# Main_PCB.net
KiCad netlist of a schematic drawn in EAGLE
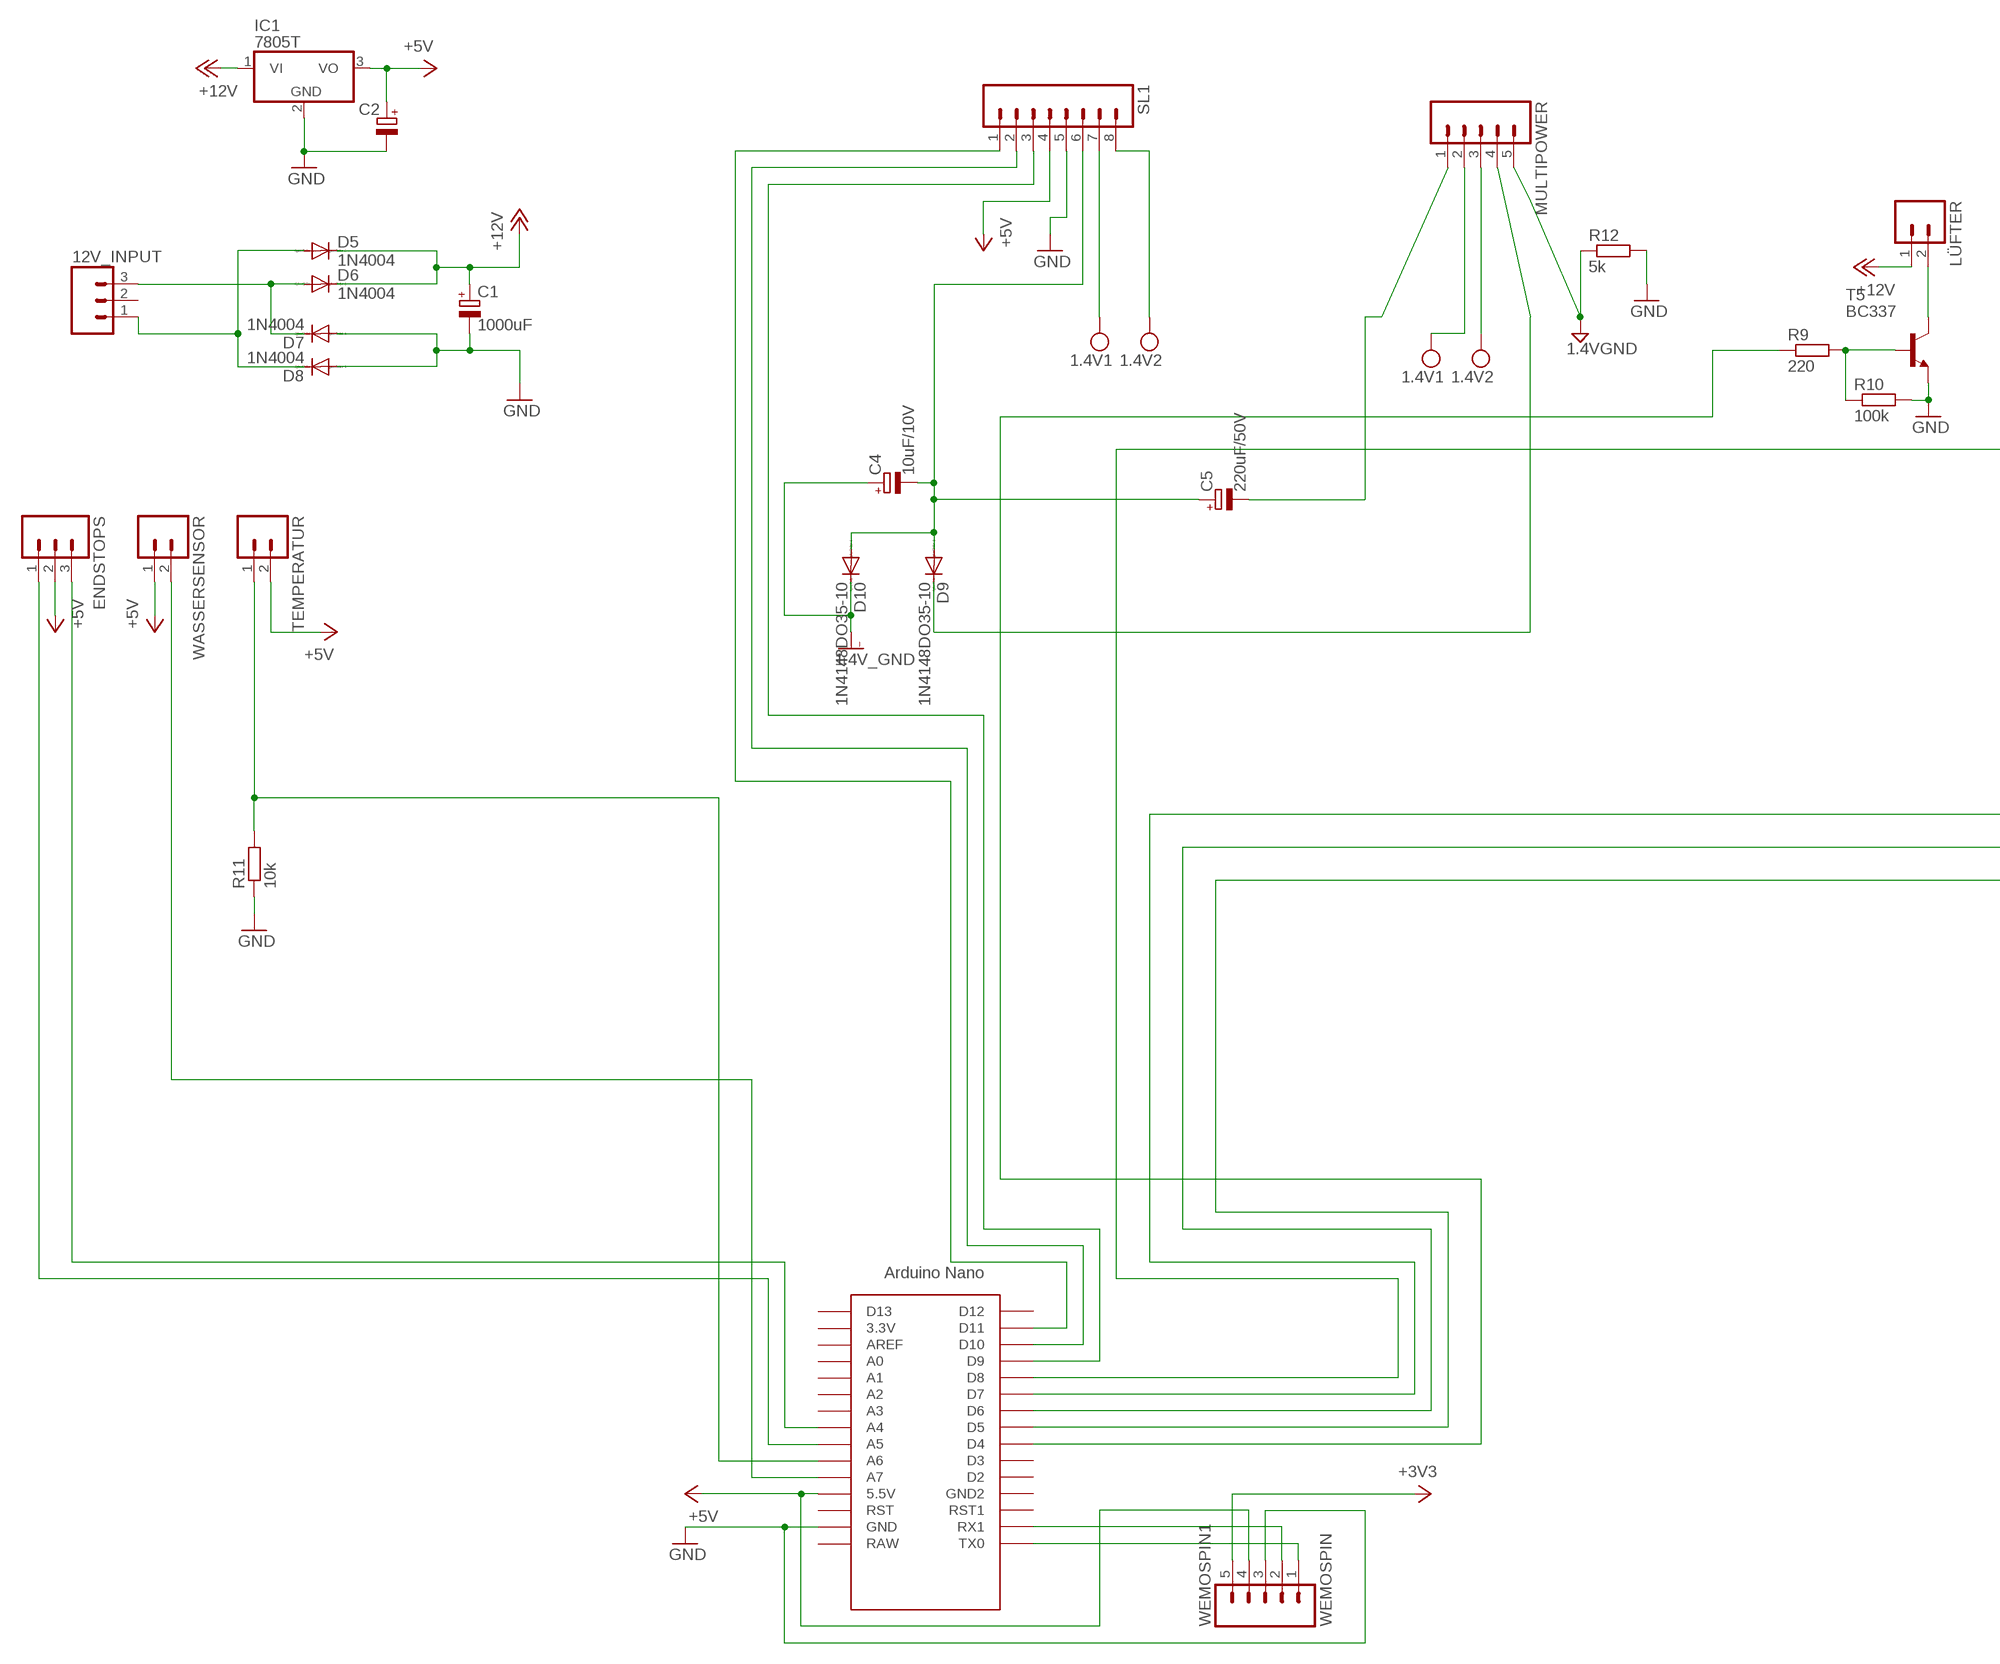
[diagram p0: schematic, sheet 1, part 1 of 2]
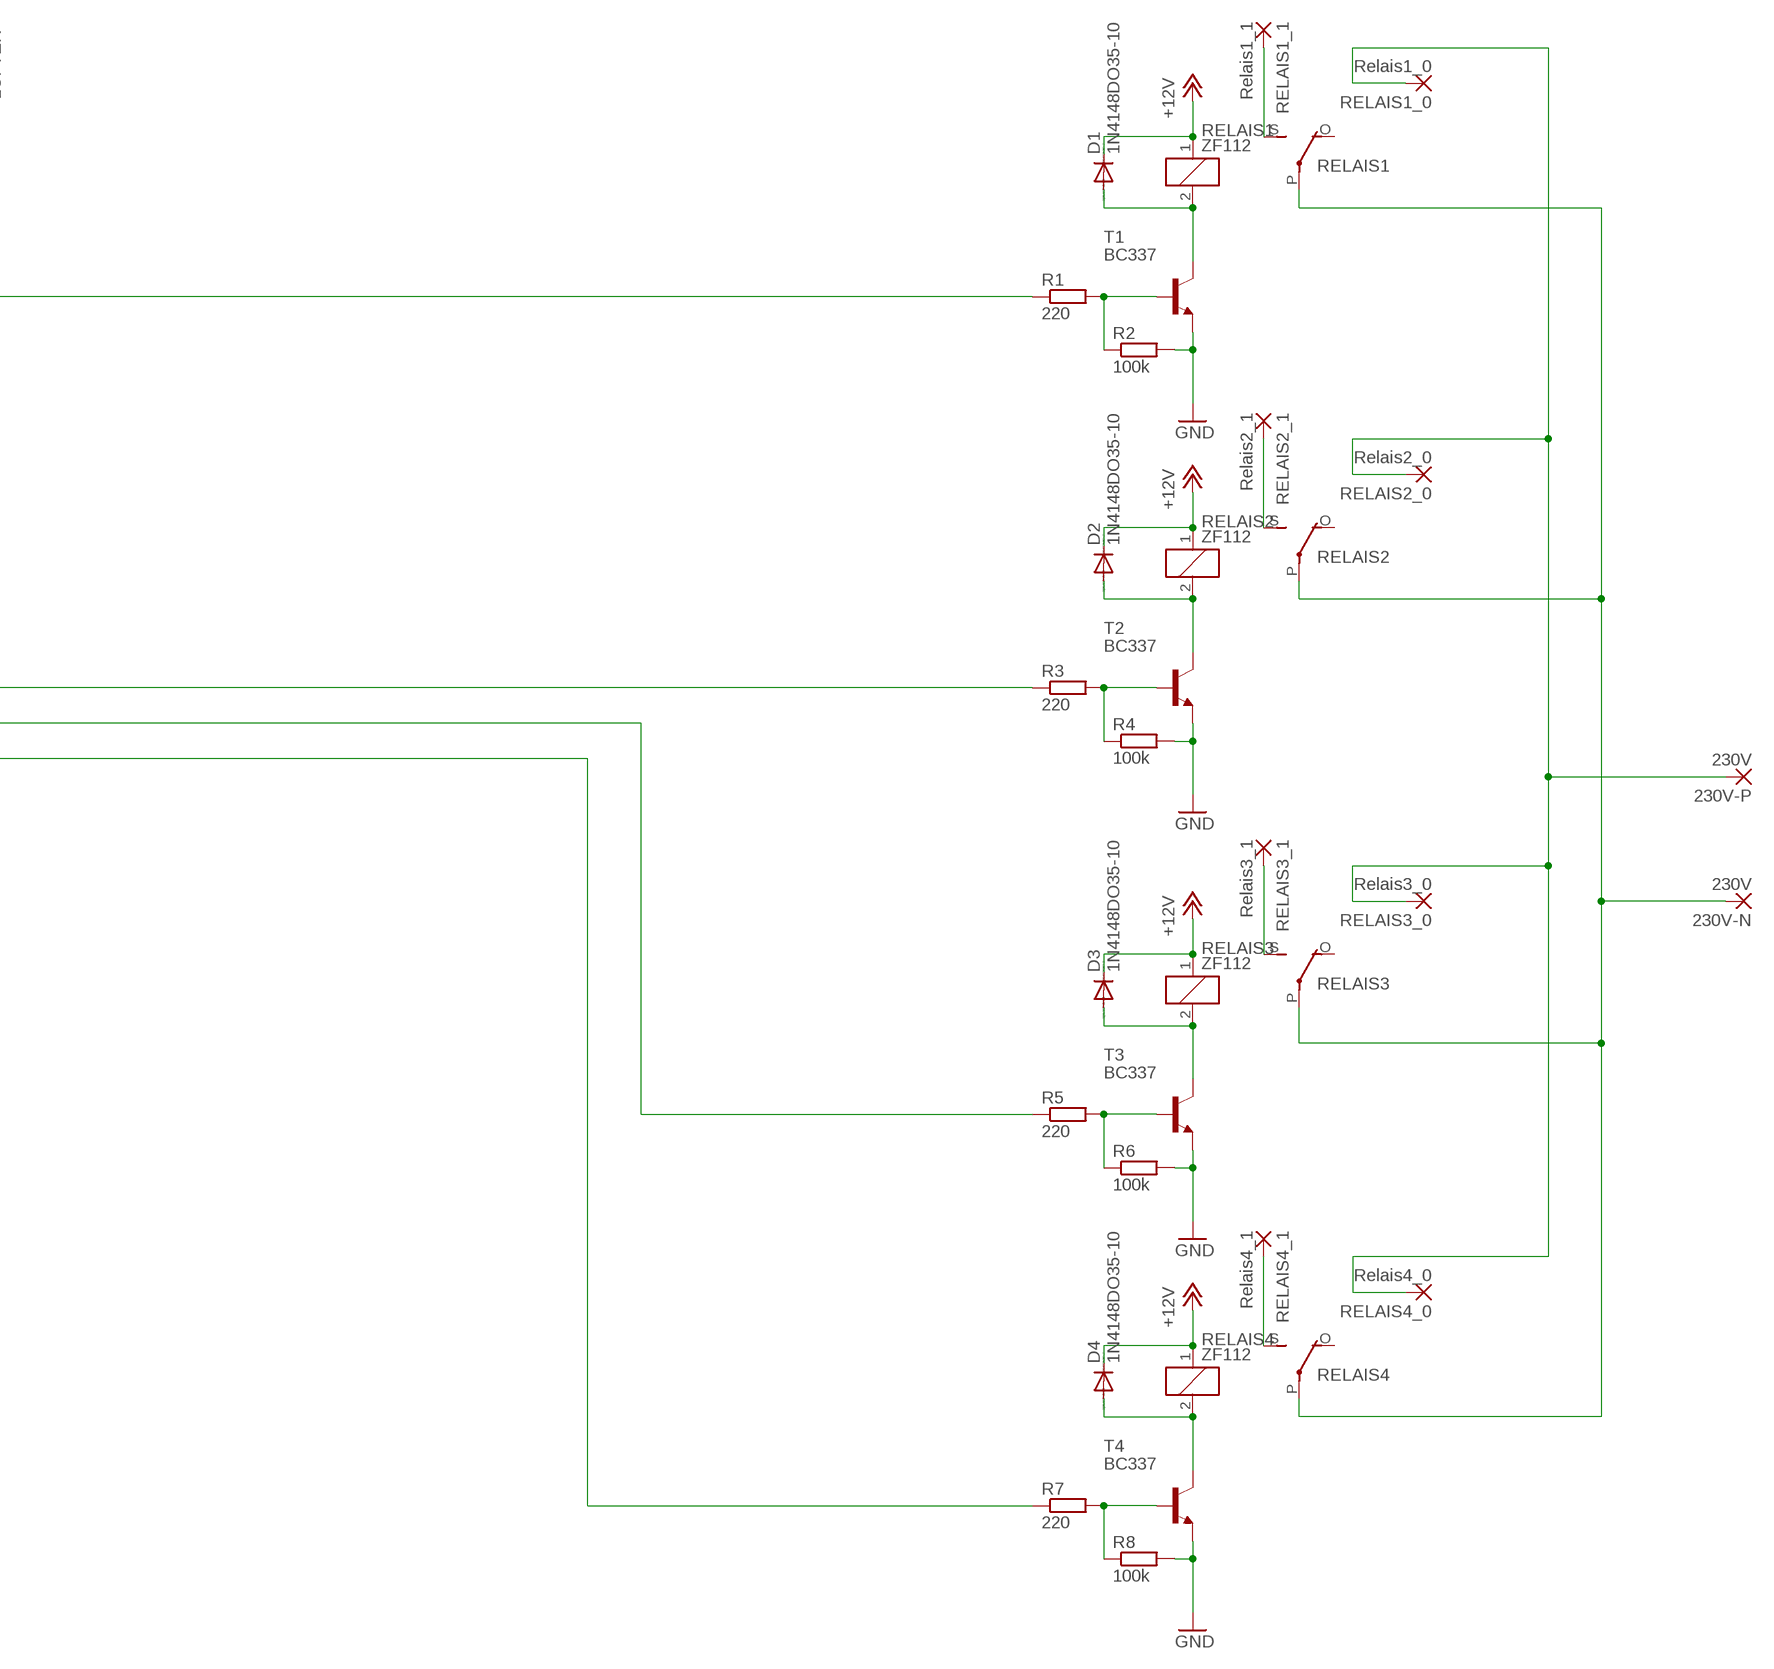
[diagram p1: schematic, sheet 1, part 2 of 2]

(export (version "E")
  (design (tool "Eeschema 10.0.6"))
  (components
    (comp (ref "12V_INPUT")
      (value "M03")
      (footprint "eagle-import:03P")
      (libsource (lib "eagle-import") (part "M03"))
    )
    (comp (ref "230V-N")
      (value "230V")
      (footprint "eagle-import:2,15_1,0")
      (libsource (lib "eagle-import") (part "2,15/1,0"))
    )
    (comp (ref "230V-P")
      (value "230V")
      (footprint "eagle-import:2,15_1,0")
      (libsource (lib "eagle-import") (part "2,15/1,0"))
    )
    (comp (ref "C1")
      (value "1000uF")
      (footprint "eagle-import:E2,5-5")
      (libsource (lib "eagle-import") (part "CPOL-EUE2.5-5"))
    )
    (comp (ref "C2")
      (value "CPOL-EUE2.5-4V")
      (footprint "eagle-import:E2,5RE")
      (libsource (lib "eagle-import") (part "resistor_348_CPOL-EUE2.5-4V"))
    )
    (comp (ref "C4")
      (value "10uF/10V")
      (footprint "eagle-import:E2,5RE")
      (libsource (lib "eagle-import") (part "CPOL-EUE2.5-4V"))
    )
    (comp (ref "C5")
      (value "220uF/50V")
      (footprint "eagle-import:E2,5RE")
      (libsource (lib "eagle-import") (part "CPOL-EUE2.5-4V"))
    )
    (comp (ref "D1")
      (value "1N4148DO35-10")
      (footprint "eagle-import:DO35-10")
      (libsource (lib "eagle-import") (part "1N4148DO35-10"))
    )
    (comp (ref "D2")
      (value "1N4148DO35-10")
      (footprint "eagle-import:DO35-10")
      (libsource (lib "eagle-import") (part "1N4148DO35-10"))
    )
    (comp (ref "D3")
      (value "1N4148DO35-10")
      (footprint "eagle-import:DO35-10")
      (libsource (lib "eagle-import") (part "1N4148DO35-10"))
    )
    (comp (ref "D4")
      (value "1N4148DO35-10")
      (footprint "eagle-import:DO35-10")
      (libsource (lib "eagle-import") (part "1N4148DO35-10"))
    )
    (comp (ref "D5")
      (value "1N4004")
      (footprint "eagle-import:DO41-10")
      (libsource (lib "eagle-import") (part "1N4004"))
    )
    (comp (ref "D6")
      (value "1N4004")
      (footprint "eagle-import:DO41-10")
      (libsource (lib "eagle-import") (part "1N4004"))
    )
    (comp (ref "D7")
      (value "1N4004")
      (footprint "eagle-import:DO41-10")
      (libsource (lib "eagle-import") (part "1N4004"))
    )
    (comp (ref "D8")
      (value "1N4004")
      (footprint "eagle-import:DO41-10")
      (libsource (lib "eagle-import") (part "1N4004"))
    )
    (comp (ref "D9")
      (value "1N4148DO35-10")
      (footprint "eagle-import:DO35-10")
      (libsource (lib "eagle-import") (part "1N4148DO35-10"))
    )
    (comp (ref "D10")
      (value "1N4148DO35-10")
      (footprint "eagle-import:DO35-10")
      (libsource (lib "eagle-import") (part "1N4148DO35-10"))
    )
    (comp (ref "ENDSTOPS")
      (value "M03")
      (footprint "eagle-import:03P")
      (libsource (lib "eagle-import") (part "M03"))
    )
    (comp (ref "IC1")
      (value "7805T")
      (footprint "eagle-import:TO220H")
      (libsource (lib "eagle-import") (part "78T05"))
    )
    (comp (ref "LÜFTER")
      (value "M02")
      (footprint "eagle-import:02P")
      (libsource (lib "eagle-import") (part "M02"))
    )
    (comp (ref "MULTIPOWER")
      (value "M05")
      (footprint "eagle-import:05P")
      (libsource (lib "eagle-import") (part "M05"))
    )
    (comp (ref "R1")
      (value "220")
      (footprint "eagle-import:0207_10")
      (libsource (lib "eagle-import") (part "R-EU_0207/10"))
    )
    (comp (ref "R2")
      (value "100k")
      (footprint "eagle-import:0207_10")
      (libsource (lib "eagle-import") (part "R-EU_0207/10"))
    )
    (comp (ref "R3")
      (value "220")
      (footprint "eagle-import:0207_10")
      (libsource (lib "eagle-import") (part "R-EU_0207/10"))
    )
    (comp (ref "R4")
      (value "100k")
      (footprint "eagle-import:0207_10")
      (libsource (lib "eagle-import") (part "R-EU_0207/10"))
    )
    (comp (ref "R5")
      (value "220")
      (footprint "eagle-import:0207_10")
      (libsource (lib "eagle-import") (part "R-EU_0207/10"))
    )
    (comp (ref "R6")
      (value "100k")
      (footprint "eagle-import:0207_10")
      (libsource (lib "eagle-import") (part "R-EU_0207/10"))
    )
    (comp (ref "R7")
      (value "220")
      (footprint "eagle-import:0207_10")
      (libsource (lib "eagle-import") (part "R-EU_0207/10"))
    )
    (comp (ref "R8")
      (value "100k")
      (footprint "eagle-import:0207_10")
      (libsource (lib "eagle-import") (part "R-EU_0207/10"))
    )
    (comp (ref "R9")
      (value "220")
      (footprint "eagle-import:0207_10")
      (libsource (lib "eagle-import") (part "R-EU_0207/10"))
    )
    (comp (ref "R10")
      (value "100k")
      (footprint "eagle-import:0207_10")
      (libsource (lib "eagle-import") (part "R-EU_0207/10"))
    )
    (comp (ref "R11")
      (value "10k")
      (footprint "eagle-import:0207_10")
      (libsource (lib "eagle-import") (part "R-EU_0207/10"))
    )
    (comp (ref "R12")
      (value "5k")
      (footprint "eagle-import:0207_10")
      (libsource (lib "eagle-import") (part "R-EU_0207/10"))
    )
    (comp (ref "RELAIS1")
      (value "ZF112")
      (footprint "eagle-import:ZF112")
      (libsource (lib "eagle-import") (part "ZF112"))
    )
    (comp (ref "RELAIS1_0")
      (value "Relais1_0")
      (footprint "eagle-import:2,15_1,0")
      (libsource (lib "eagle-import") (part "2,15/1,0"))
    )
    (comp (ref "RELAIS1_1")
      (value "Relais1_1")
      (footprint "eagle-import:2,15_1,0")
      (libsource (lib "eagle-import") (part "2,15/1,0"))
    )
    (comp (ref "RELAIS2")
      (value "ZF112")
      (footprint "eagle-import:ZF112")
      (libsource (lib "eagle-import") (part "ZF112"))
    )
    (comp (ref "RELAIS2_0")
      (value "Relais2_0")
      (footprint "eagle-import:2,15_1,0")
      (libsource (lib "eagle-import") (part "2,15/1,0"))
    )
    (comp (ref "RELAIS2_1")
      (value "Relais2_1")
      (footprint "eagle-import:2,15_1,0")
      (libsource (lib "eagle-import") (part "2,15/1,0"))
    )
    (comp (ref "RELAIS3")
      (value "ZF112")
      (footprint "eagle-import:ZF112")
      (libsource (lib "eagle-import") (part "ZF112"))
    )
    (comp (ref "RELAIS3_0")
      (value "Relais3_0")
      (footprint "eagle-import:2,15_1,0")
      (libsource (lib "eagle-import") (part "2,15/1,0"))
    )
    (comp (ref "RELAIS3_1")
      (value "Relais3_1")
      (footprint "eagle-import:2,15_1,0")
      (libsource (lib "eagle-import") (part "2,15/1,0"))
    )
    (comp (ref "RELAIS4")
      (value "ZF112")
      (footprint "eagle-import:ZF112")
      (libsource (lib "eagle-import") (part "ZF112"))
    )
    (comp (ref "RELAIS4_0")
      (value "Relais4_0")
      (footprint "eagle-import:2,15_1,0")
      (libsource (lib "eagle-import") (part "2,15/1,0"))
    )
    (comp (ref "RELAIS4_1")
      (value "Relais4_1")
      (footprint "eagle-import:2,15_1,0")
      (libsource (lib "eagle-import") (part "2,15/1,0"))
    )
    (comp (ref "SL1")
      (value "M08")
      (footprint "eagle-import:08P")
      (libsource (lib "eagle-import") (part "M08"))
    )
    (comp (ref "T1")
      (value "BC337")
      (footprint "eagle-import:TO92")
      (libsource (lib "eagle-import") (part "BC337"))
    )
    (comp (ref "T2")
      (value "BC337")
      (footprint "eagle-import:TO92")
      (libsource (lib "eagle-import") (part "BC337"))
    )
    (comp (ref "T3")
      (value "BC337")
      (footprint "eagle-import:TO92")
      (libsource (lib "eagle-import") (part "BC337"))
    )
    (comp (ref "T4")
      (value "BC337")
      (footprint "eagle-import:TO92")
      (libsource (lib "eagle-import") (part "BC337"))
    )
    (comp (ref "T5")
      (value "BC337")
      (footprint "eagle-import:TO92")
      (libsource (lib "eagle-import") (part "BC337"))
    )
    (comp (ref "TEMPERATUR")
      (value "M02")
      (footprint "eagle-import:02P")
      (libsource (lib "eagle-import") (part "M02"))
    )
    (comp (ref "U$1")
      (value "NANO")
      (footprint "eagle-import:NANO")
      (libsource (lib "eagle-import") (part "NANO"))
    )
    (comp (ref "WASSERSENSOR")
      (value "M02")
      (footprint "eagle-import:02P")
      (libsource (lib "eagle-import") (part "M02"))
    )
    (comp (ref "WEMOSPIN1")
      (value "WEMOSPIN")
      (footprint "eagle-import:05P")
      (libsource (lib "eagle-import") (part "M05"))
    )
  )
  (nets
    (net (code "1") (name "+3V3") (class "Default")
      (node (ref "WEMOSPIN1") (pin "5") (pinfunction "5_5") (pintype "passive"))
    )
    (net (code "2") (name "+5V") (class "Default")
      (node (ref "C2") (pin "+") (pinfunction "+_+") (pintype "passive"))
      (node (ref "ENDSTOPS") (pin "2") (pinfunction "2_2") (pintype "passive"))
      (node (ref "IC1") (pin "3") (pinfunction "VO_3") (pintype "passive"))
      (node (ref "SL1") (pin "4") (pinfunction "4_4") (pintype "passive"))
      (node (ref "TEMPERATUR") (pin "2") (pinfunction "2_2") (pintype "passive"))
      (node (ref "U$1") (pin "5V") (pinfunction "5.5V_5V") (pintype "bidirectional"))
      (node (ref "WASSERSENSOR") (pin "1") (pinfunction "1_1") (pintype "passive"))
      (node (ref "WEMOSPIN1") (pin "4") (pinfunction "4_4") (pintype "passive"))
    )
    (net (code "3") (name "+12V") (class "Default")
      (node (ref "C1") (pin "+") (pinfunction "+_+") (pintype "passive"))
      (node (ref "D1") (pin "C") (pinfunction "C_C") (pintype "passive"))
      (node (ref "D2") (pin "C") (pinfunction "C_C") (pintype "passive"))
      (node (ref "D3") (pin "C") (pinfunction "C_C") (pintype "passive"))
      (node (ref "D4") (pin "C") (pinfunction "C_C") (pintype "passive"))
      (node (ref "D5") (pin "C") (pinfunction "C_C") (pintype "passive"))
      (node (ref "D6") (pin "C") (pinfunction "C_C") (pintype "passive"))
      (node (ref "IC1") (pin "1") (pinfunction "VI_1") (pintype "input"))
      (node (ref "LÜFTER") (pin "1") (pinfunction "1_1") (pintype "passive"))
      (node (ref "RELAIS1") (pin "1") (pinfunction "1_1") (pintype "passive"))
      (node (ref "RELAIS2") (pin "1") (pinfunction "1_1") (pintype "passive"))
      (node (ref "RELAIS3") (pin "1") (pinfunction "1_1") (pintype "passive"))
      (node (ref "RELAIS4") (pin "1") (pinfunction "1_1") (pintype "passive"))
    )
    (net (code "4") (name "1.4V1") (class "Default")
      (node (ref "MULTIPOWER") (pin "2") (pinfunction "2_2") (pintype "passive"))
      (node (ref "SL1") (pin "7") (pinfunction "7_7") (pintype "passive"))
    )
    (net (code "5") (name "1.4V2") (class "Default")
      (node (ref "MULTIPOWER") (pin "3") (pinfunction "3_3") (pintype "passive"))
      (node (ref "SL1") (pin "8") (pinfunction "8_8") (pintype "passive"))
    )
    (net (code "6") (name "1.4VGND") (class "Default")
      (node (ref "MULTIPOWER") (pin "5") (pinfunction "5_5") (pintype "passive"))
      (node (ref "R12") (pin "1") (pinfunction "1_1") (pintype "passive"))
    )
    (net (code "7") (name "1.4V_GND") (class "Default")
      (node (ref "C4") (pin "+") (pinfunction "+_+") (pintype "passive"))
      (node (ref "D10") (pin "C") (pinfunction "C_C") (pintype "passive"))
    )
    (net (code "8") (name "GND") (class "Default")
      (node (ref "C1") (pin "-") (pinfunction "-_-") (pintype "passive"))
      (node (ref "C2") (pin "-") (pinfunction "-_-") (pintype "passive"))
      (node (ref "D7") (pin "A") (pinfunction "A_A") (pintype "passive"))
      (node (ref "D8") (pin "A") (pinfunction "A_A") (pintype "passive"))
      (node (ref "IC1") (pin "2") (pinfunction "GND_2") (pintype "passive"))
      (node (ref "R10") (pin "2") (pinfunction "2_2") (pintype "passive"))
      (node (ref "R11") (pin "1") (pinfunction "1_1") (pintype "passive"))
      (node (ref "R12") (pin "2") (pinfunction "2_2") (pintype "passive"))
      (node (ref "R2") (pin "2") (pinfunction "2_2") (pintype "passive"))
      (node (ref "R4") (pin "2") (pinfunction "2_2") (pintype "passive"))
      (node (ref "R6") (pin "2") (pinfunction "2_2") (pintype "passive"))
      (node (ref "R8") (pin "2") (pinfunction "2_2") (pintype "passive"))
      (node (ref "SL1") (pin "5") (pinfunction "5_5") (pintype "passive"))
      (node (ref "T1") (pin "1") (pinfunction "E_1") (pintype "passive"))
      (node (ref "T2") (pin "1") (pinfunction "E_1") (pintype "passive"))
      (node (ref "T3") (pin "1") (pinfunction "E_1") (pintype "passive"))
      (node (ref "T4") (pin "1") (pinfunction "E_1") (pintype "passive"))
      (node (ref "T5") (pin "1") (pinfunction "E_1") (pintype "passive"))
      (node (ref "U$1") (pin "GND") (pinfunction "GND_GND") (pintype "bidirectional"))
      (node (ref "WEMOSPIN1") (pin "3") (pinfunction "3_3") (pintype "passive"))
    )
    (net (code "9") (name "Net-(12V_INPUT-Pad1)") (class "Default")
      (node (ref "12V_INPUT") (pin "1") (pinfunction "1_1") (pintype "passive"))
      (node (ref "D5") (pin "A") (pinfunction "A_A") (pintype "passive"))
      (node (ref "D8") (pin "C") (pinfunction "C_C") (pintype "passive"))
    )
    (net (code "10") (name "Net-(12V_INPUT-Pad3)") (class "Default")
      (node (ref "12V_INPUT") (pin "3") (pinfunction "3_3") (pintype "passive"))
      (node (ref "D6") (pin "A") (pinfunction "A_A") (pintype "passive"))
      (node (ref "D7") (pin "C") (pinfunction "C_C") (pintype "passive"))
    )
    (net (code "11") (name "Net-(230V-N-P)") (class "Default")
      (node (ref "230V-N") (pin "1") (pinfunction "P_1") (pintype "passive"))
      (node (ref "RELAIS1") (pin "P") (pinfunction "P_P") (pintype "passive"))
      (node (ref "RELAIS2") (pin "P") (pinfunction "P_P") (pintype "passive"))
      (node (ref "RELAIS3") (pin "P") (pinfunction "P_P") (pintype "passive"))
      (node (ref "RELAIS4") (pin "P") (pinfunction "P_P") (pintype "passive"))
    )
    (net (code "12") (name "Net-(230V-P-P)") (class "Default")
      (node (ref "230V-P") (pin "1") (pinfunction "P_1") (pintype "passive"))
      (node (ref "RELAIS1_0") (pin "1") (pinfunction "P_1") (pintype "passive"))
      (node (ref "RELAIS2_0") (pin "1") (pinfunction "P_1") (pintype "passive"))
      (node (ref "RELAIS3_0") (pin "1") (pinfunction "P_1") (pintype "passive"))
      (node (ref "RELAIS4_0") (pin "1") (pinfunction "P_1") (pintype "passive"))
    )
    (net (code "13") (name "Net-(C4-Pad-)") (class "Default")
      (node (ref "C4") (pin "-") (pinfunction "-_-") (pintype "passive"))
      (node (ref "C5") (pin "+") (pinfunction "+_+") (pintype "passive"))
      (node (ref "D10") (pin "A") (pinfunction "A_A") (pintype "passive"))
      (node (ref "D9") (pin "A") (pinfunction "A_A") (pintype "passive"))
      (node (ref "SL1") (pin "6") (pinfunction "6_6") (pintype "passive"))
    )
    (net (code "14") (name "Net-(C5-Pad-)") (class "Default")
      (node (ref "C5") (pin "-") (pinfunction "-_-") (pintype "passive"))
      (node (ref "MULTIPOWER") (pin "1") (pinfunction "1_1") (pintype "passive"))
    )
    (net (code "15") (name "Net-(D9-PadC)") (class "Default")
      (node (ref "D9") (pin "C") (pinfunction "C_C") (pintype "passive"))
      (node (ref "MULTIPOWER") (pin "4") (pinfunction "4_4") (pintype "passive"))
    )
    (net (code "16") (name "Net-(ENDSTOPS-Pad1)") (class "Default")
      (node (ref "ENDSTOPS") (pin "1") (pinfunction "1_1") (pintype "passive"))
      (node (ref "U$1") (pin "A5") (pinfunction "A5_A5") (pintype "bidirectional"))
    )
    (net (code "17") (name "Net-(ENDSTOPS-Pad3)") (class "Default")
      (node (ref "ENDSTOPS") (pin "3") (pinfunction "3_3") (pintype "passive"))
      (node (ref "U$1") (pin "A4") (pinfunction "A4_A4") (pintype "bidirectional"))
    )
    (net (code "18") (name "Net-(R1-Pad1)") (class "Default")
      (node (ref "R1") (pin "1") (pinfunction "1_1") (pintype "passive"))
      (node (ref "U$1") (pin "D8") (pinfunction "D8_D8") (pintype "bidirectional"))
    )
    (net (code "19") (name "Net-(R3-Pad1)") (class "Default")
      (node (ref "R3") (pin "1") (pinfunction "1_1") (pintype "passive"))
      (node (ref "U$1") (pin "D7") (pinfunction "D7_D7") (pintype "bidirectional"))
    )
    (net (code "20") (name "Net-(R5-Pad1)") (class "Default")
      (node (ref "R5") (pin "1") (pinfunction "1_1") (pintype "passive"))
      (node (ref "U$1") (pin "D6") (pinfunction "D6_D6") (pintype "bidirectional"))
    )
    (net (code "21") (name "Net-(R7-Pad1)") (class "Default")
      (node (ref "R7") (pin "1") (pinfunction "1_1") (pintype "passive"))
      (node (ref "U$1") (pin "D5") (pinfunction "D5_D5") (pintype "bidirectional"))
    )
    (net (code "22") (name "Net-(R9-Pad1)") (class "Default")
      (node (ref "R9") (pin "1") (pinfunction "1_1") (pintype "passive"))
      (node (ref "U$1") (pin "D4") (pinfunction "D4_D4") (pintype "bidirectional"))
    )
    (net (code "23") (name "Net-(R11-Pad2)") (class "Default")
      (node (ref "R11") (pin "2") (pinfunction "2_2") (pintype "passive"))
      (node (ref "TEMPERATUR") (pin "1") (pinfunction "1_1") (pintype "passive"))
      (node (ref "U$1") (pin "A6") (pinfunction "A6_A6") (pintype "bidirectional"))
    )
    (net (code "24") (name "Net-(RELAIS1_1-P)") (class "Default")
      (node (ref "RELAIS1") (pin "S") (pinfunction "S_S") (pintype "passive"))
      (node (ref "RELAIS1_1") (pin "1") (pinfunction "P_1") (pintype "passive"))
    )
    (net (code "25") (name "Net-(RELAIS2_1-P)") (class "Default")
      (node (ref "RELAIS2") (pin "S") (pinfunction "S_S") (pintype "passive"))
      (node (ref "RELAIS2_1") (pin "1") (pinfunction "P_1") (pintype "passive"))
    )
    (net (code "26") (name "Net-(RELAIS3_1-P)") (class "Default")
      (node (ref "RELAIS3") (pin "S") (pinfunction "S_S") (pintype "passive"))
      (node (ref "RELAIS3_1") (pin "1") (pinfunction "P_1") (pintype "passive"))
    )
    (net (code "27") (name "Net-(RELAIS4_1-P)") (class "Default")
      (node (ref "RELAIS4") (pin "S") (pinfunction "S_S") (pintype "passive"))
      (node (ref "RELAIS4_1") (pin "1") (pinfunction "P_1") (pintype "passive"))
    )
    (net (code "28") (name "Net-(SL1-Pad1)") (class "Default")
      (node (ref "SL1") (pin "1") (pinfunction "1_1") (pintype "passive"))
      (node (ref "U$1") (pin "D11") (pinfunction "D11_D11") (pintype "bidirectional"))
    )
    (net (code "29") (name "Net-(SL1-Pad2)") (class "Default")
      (node (ref "SL1") (pin "2") (pinfunction "2_2") (pintype "passive"))
      (node (ref "U$1") (pin "D10") (pinfunction "D10_D10") (pintype "bidirectional"))
    )
    (net (code "30") (name "Net-(SL1-Pad3)") (class "Default")
      (node (ref "SL1") (pin "3") (pinfunction "3_3") (pintype "passive"))
      (node (ref "U$1") (pin "D9") (pinfunction "D9_D9") (pintype "bidirectional"))
    )
    (net (code "31") (name "Net-(T1-B)") (class "Default")
      (node (ref "R1") (pin "2") (pinfunction "2_2") (pintype "passive"))
      (node (ref "R2") (pin "1") (pinfunction "1_1") (pintype "passive"))
      (node (ref "T1") (pin "2") (pinfunction "B_2") (pintype "passive"))
    )
    (net (code "32") (name "Net-(T1-C)") (class "Default")
      (node (ref "D1") (pin "A") (pinfunction "A_A") (pintype "passive"))
      (node (ref "RELAIS1") (pin "2") (pinfunction "2_2") (pintype "passive"))
      (node (ref "T1") (pin "3") (pinfunction "C_3") (pintype "passive"))
    )
    (net (code "33") (name "Net-(T2-B)") (class "Default")
      (node (ref "R3") (pin "2") (pinfunction "2_2") (pintype "passive"))
      (node (ref "R4") (pin "1") (pinfunction "1_1") (pintype "passive"))
      (node (ref "T2") (pin "2") (pinfunction "B_2") (pintype "passive"))
    )
    (net (code "34") (name "Net-(T2-C)") (class "Default")
      (node (ref "D2") (pin "A") (pinfunction "A_A") (pintype "passive"))
      (node (ref "RELAIS2") (pin "2") (pinfunction "2_2") (pintype "passive"))
      (node (ref "T2") (pin "3") (pinfunction "C_3") (pintype "passive"))
    )
    (net (code "35") (name "Net-(T3-B)") (class "Default")
      (node (ref "R5") (pin "2") (pinfunction "2_2") (pintype "passive"))
      (node (ref "R6") (pin "1") (pinfunction "1_1") (pintype "passive"))
      (node (ref "T3") (pin "2") (pinfunction "B_2") (pintype "passive"))
    )
    (net (code "36") (name "Net-(T3-C)") (class "Default")
      (node (ref "D3") (pin "A") (pinfunction "A_A") (pintype "passive"))
      (node (ref "RELAIS3") (pin "2") (pinfunction "2_2") (pintype "passive"))
      (node (ref "T3") (pin "3") (pinfunction "C_3") (pintype "passive"))
    )
    (net (code "37") (name "Net-(T4-B)") (class "Default")
      (node (ref "R7") (pin "2") (pinfunction "2_2") (pintype "passive"))
      (node (ref "R8") (pin "1") (pinfunction "1_1") (pintype "passive"))
      (node (ref "T4") (pin "2") (pinfunction "B_2") (pintype "passive"))
    )
    (net (code "38") (name "Net-(T4-C)") (class "Default")
      (node (ref "D4") (pin "A") (pinfunction "A_A") (pintype "passive"))
      (node (ref "RELAIS4") (pin "2") (pinfunction "2_2") (pintype "passive"))
      (node (ref "T4") (pin "3") (pinfunction "C_3") (pintype "passive"))
    )
    (net (code "39") (name "Net-(T5-B)") (class "Default")
      (node (ref "R10") (pin "1") (pinfunction "1_1") (pintype "passive"))
      (node (ref "R9") (pin "2") (pinfunction "2_2") (pintype "passive"))
      (node (ref "T5") (pin "2") (pinfunction "B_2") (pintype "passive"))
    )
    (net (code "40") (name "Net-(T5-C)") (class "Default")
      (node (ref "LÜFTER") (pin "2") (pinfunction "2_2") (pintype "passive"))
      (node (ref "T5") (pin "3") (pinfunction "C_3") (pintype "passive"))
    )
    (net (code "41") (name "Net-(U$1-PadA7)") (class "Default")
      (node (ref "U$1") (pin "A7") (pinfunction "A7_A7") (pintype "bidirectional"))
      (node (ref "WASSERSENSOR") (pin "2") (pinfunction "2_2") (pintype "passive"))
    )
    (net (code "42") (name "Net-(U$1-PadRX1)") (class "Default")
      (node (ref "U$1") (pin "RX1") (pinfunction "RX1_RX1") (pintype "bidirectional"))
      (node (ref "WEMOSPIN1") (pin "2") (pinfunction "2_2") (pintype "passive"))
    )
    (net (code "43") (name "Net-(U$1-PadTX0)") (class "Default")
      (node (ref "U$1") (pin "TX0") (pinfunction "TX0_TX0") (pintype "bidirectional"))
      (node (ref "WEMOSPIN1") (pin "1") (pinfunction "1_1") (pintype "passive"))
    )
    (net (code "44") (name "unconnected-(12V_INPUT-Pad2)") (class "Default")
      (node (ref "12V_INPUT") (pin "2") (pinfunction "2_2") (pintype "passive"))
    )
    (net (code "45") (name "unconnected-(RELAIS1-PadO)") (class "Default")
      (node (ref "RELAIS1") (pin "O") (pinfunction "O_O") (pintype "passive"))
    )
    (net (code "46") (name "unconnected-(RELAIS2-PadO)") (class "Default")
      (node (ref "RELAIS2") (pin "O") (pinfunction "O_O") (pintype "passive"))
    )
    (net (code "47") (name "unconnected-(RELAIS3-PadO)") (class "Default")
      (node (ref "RELAIS3") (pin "O") (pinfunction "O_O") (pintype "passive"))
    )
    (net (code "48") (name "unconnected-(RELAIS4-PadO)") (class "Default")
      (node (ref "RELAIS4") (pin "O") (pinfunction "O_O") (pintype "passive"))
    )
    (net (code "49") (name "unconnected-(U$1-GND2-PadGND1)") (class "Default")
      (node (ref "U$1") (pin "GND1") (pinfunction "GND2_GND1") (pintype "bidirectional"))
    )
    (net (code "50") (name "unconnected-(U$1-Pad3.3V)") (class "Default")
      (node (ref "U$1") (pin "3.3V") (pinfunction "3.3V_3.3V") (pintype "bidirectional"))
    )
    (net (code "51") (name "unconnected-(U$1-PadA0)") (class "Default")
      (node (ref "U$1") (pin "A0") (pinfunction "A0_A0") (pintype "bidirectional"))
    )
    (net (code "52") (name "unconnected-(U$1-PadA1)") (class "Default")
      (node (ref "U$1") (pin "A1") (pinfunction "A1_A1") (pintype "bidirectional"))
    )
    (net (code "53") (name "unconnected-(U$1-PadA2)") (class "Default")
      (node (ref "U$1") (pin "A2") (pinfunction "A2_A2") (pintype "bidirectional"))
    )
    (net (code "54") (name "unconnected-(U$1-PadA3)") (class "Default")
      (node (ref "U$1") (pin "A3") (pinfunction "A3_A3") (pintype "bidirectional"))
    )
    (net (code "55") (name "unconnected-(U$1-PadAREF)") (class "Default")
      (node (ref "U$1") (pin "AREF") (pinfunction "AREF_AREF") (pintype "bidirectional"))
    )
    (net (code "56") (name "unconnected-(U$1-PadD2)") (class "Default")
      (node (ref "U$1") (pin "D2") (pinfunction "D2_D2") (pintype "bidirectional"))
    )
    (net (code "57") (name "unconnected-(U$1-PadD3)") (class "Default")
      (node (ref "U$1") (pin "D3") (pinfunction "D3_D3") (pintype "bidirectional"))
    )
    (net (code "58") (name "unconnected-(U$1-PadD12)") (class "Default")
      (node (ref "U$1") (pin "D12") (pinfunction "D12_D12") (pintype "bidirectional"))
    )
    (net (code "59") (name "unconnected-(U$1-PadD13)") (class "Default")
      (node (ref "U$1") (pin "D13") (pinfunction "D13_D13") (pintype "bidirectional"))
    )
    (net (code "60") (name "unconnected-(U$1-PadICSP1)") (class "Default")
      (node (ref "U$1") (pin "ICSP1") (pinfunction "ICSP1_ICSP1") (pintype "bidirectional"))
    )
    (net (code "61") (name "unconnected-(U$1-PadICSP2)") (class "Default")
      (node (ref "U$1") (pin "ICSP2") (pinfunction "ICSP2_ICSP2") (pintype "bidirectional"))
    )
    (net (code "62") (name "unconnected-(U$1-PadICSP3)") (class "Default")
      (node (ref "U$1") (pin "ICSP3") (pinfunction "ICSP3_ICSP3") (pintype "bidirectional"))
    )
    (net (code "63") (name "unconnected-(U$1-PadICSP4)") (class "Default")
      (node (ref "U$1") (pin "ICSP4") (pinfunction "ICSP4_ICSP4") (pintype "bidirectional"))
    )
    (net (code "64") (name "unconnected-(U$1-PadICSP5)") (class "Default")
      (node (ref "U$1") (pin "ICSP5") (pinfunction "ICSP5_ICSP5") (pintype "bidirectional"))
    )
    (net (code "65") (name "unconnected-(U$1-PadICSP6)") (class "Default")
      (node (ref "U$1") (pin "ICSP6") (pinfunction "ICSP6_ICSP6") (pintype "bidirectional"))
    )
    (net (code "66") (name "unconnected-(U$1-PadRAW)") (class "Default")
      (node (ref "U$1") (pin "RAW") (pinfunction "RAW_RAW") (pintype "bidirectional"))
    )
    (net (code "67") (name "unconnected-(U$1-PadRST)") (class "Default")
      (node (ref "U$1") (pin "RST") (pinfunction "RST_RST") (pintype "bidirectional"))
    )
    (net (code "68") (name "unconnected-(U$1-PadRST1)") (class "Default")
      (node (ref "U$1") (pin "RST1") (pinfunction "RST1_RST1") (pintype "bidirectional"))
    )
  )
)
